# PCB_Sensor_Board_2_x_BME280_680_ATH10_HD.net
KiCad netlist of a schematic drawn in EAGLE
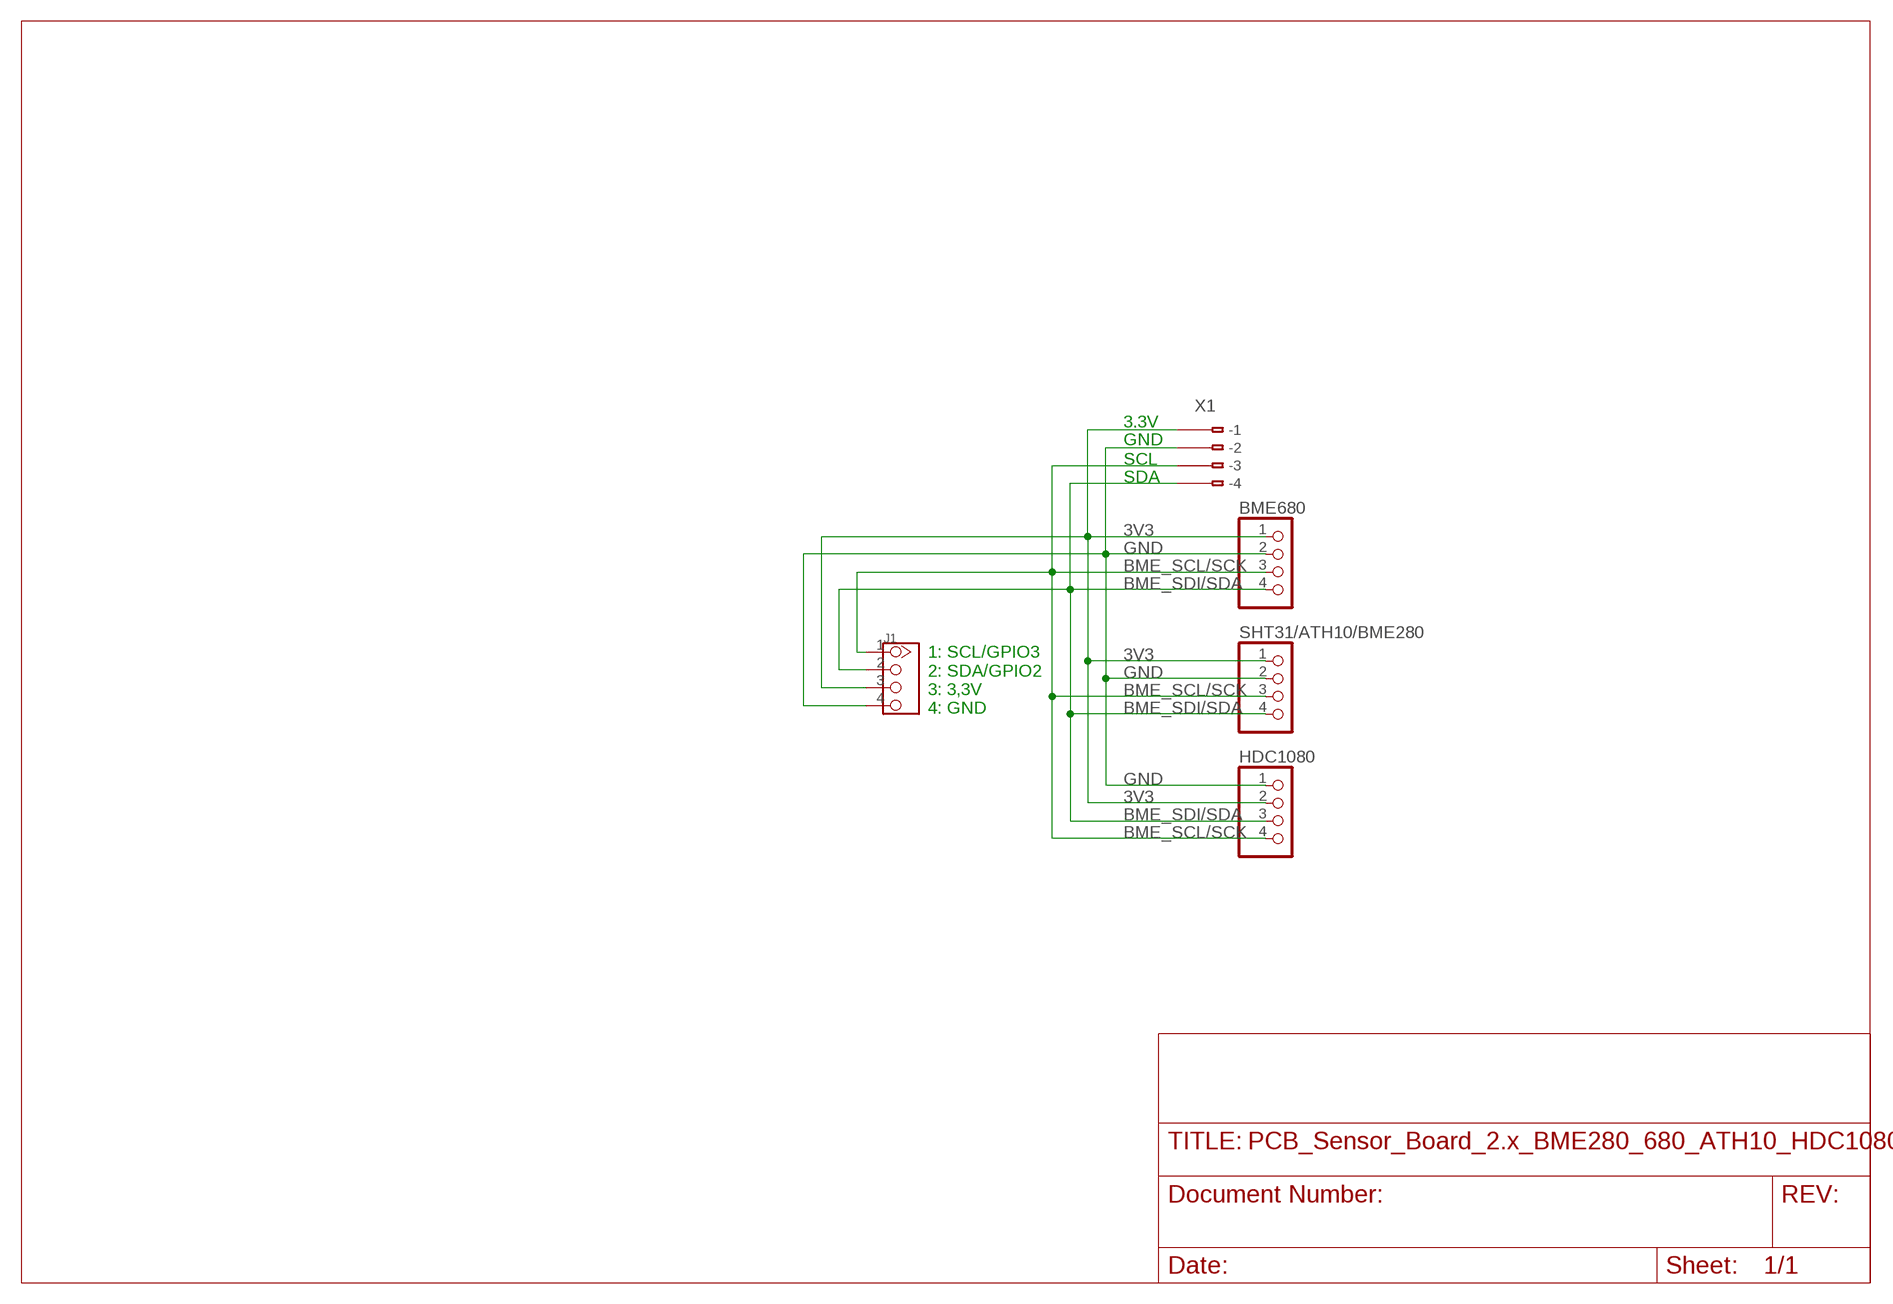
[diagram p0: schematic, sheet 1]

(export (version "E")
  (design (tool "Eeschema 10.0.6"))
  (components
    (comp (ref "BME680")
      (value "PINHD-1X4")
      (footprint "eagle-import:1X04")
      (libsource (lib "eagle-import") (part "PINHD-1X4"))
    )
    (comp (ref "HDC1080")
      (value "PINHD-1X4")
      (footprint "eagle-import:1X04")
      (libsource (lib "eagle-import") (part "PINHD-1X4"))
    )
    (comp (ref "J1")
      (value "TWIG-4P-2.0-2.0")
      (footprint "eagle-import:4P-2.0")
      (libsource (lib "eagle-import") (part "TWIG-4P-2.0-2.0"))
    )
    (comp (ref "SHT31/ATH10/BME280")
      (value "PINHD-1X4")
      (footprint "eagle-import:1X04")
      (libsource (lib "eagle-import") (part "PINHD-1X4"))
    )
    (comp (ref "X1")
      (value "233-504")
      (footprint "eagle-import:233-504")
      (fields (field (name "MF") "Wago Corporation") (field (name "MPN") "0233-0504"))
      (libsource (lib "eagle-import") (part "233-504"))
    )
  )
  (nets
    (net (code "1") (name "/3V3") (class "Default")
      (node (ref "BME680") (pin "1") (pinfunction "1_1") (pintype "passive"))
      (node (ref "HDC1080") (pin "2") (pinfunction "2_2") (pintype "passive"))
      (node (ref "J1") (pin "3") (pinfunction "3_3") (pintype "bidirectional"))
      (node (ref "SHT31/ATH10/BME280") (pin "1") (pinfunction "1_1") (pintype "passive"))
      (node (ref "X1") (pin "B1") (pinfunction "B-1_B1") (pintype "passive"))
    )
    (net (code "2") (name "/BME_SCL{slash}SCK") (class "Default")
      (node (ref "BME680") (pin "3") (pinfunction "3_3") (pintype "passive"))
      (node (ref "HDC1080") (pin "4") (pinfunction "4_4") (pintype "passive"))
      (node (ref "J1") (pin "1") (pinfunction "1_1") (pintype "bidirectional"))
      (node (ref "SHT31/ATH10/BME280") (pin "3") (pinfunction "3_3") (pintype "passive"))
      (node (ref "X1") (pin "B3") (pinfunction "B-3_B3") (pintype "passive"))
    )
    (net (code "3") (name "/BME_SDI{slash}SDA") (class "Default")
      (node (ref "BME680") (pin "4") (pinfunction "4_4") (pintype "passive"))
      (node (ref "HDC1080") (pin "3") (pinfunction "3_3") (pintype "passive"))
      (node (ref "J1") (pin "2") (pinfunction "2_2") (pintype "bidirectional"))
      (node (ref "SHT31/ATH10/BME280") (pin "4") (pinfunction "4_4") (pintype "passive"))
      (node (ref "X1") (pin "B4") (pinfunction "B-4_B4") (pintype "passive"))
    )
    (net (code "4") (name "/GND") (class "Default")
      (node (ref "BME680") (pin "2") (pinfunction "2_2") (pintype "passive"))
      (node (ref "HDC1080") (pin "1") (pinfunction "1_1") (pintype "passive"))
      (node (ref "J1") (pin "4") (pinfunction "4_4") (pintype "bidirectional"))
      (node (ref "SHT31/ATH10/BME280") (pin "2") (pinfunction "2_2") (pintype "passive"))
      (node (ref "X1") (pin "B2") (pinfunction "B-2_B2") (pintype "passive"))
    )
    (net (code "5") (name "unconnected-(X1--1-PadA1)") (class "Default")
      (node (ref "X1") (pin "A1") (pinfunction "-1_A1") (pintype "passive"))
    )
    (net (code "6") (name "unconnected-(X1--2-PadA2)") (class "Default")
      (node (ref "X1") (pin "A2") (pinfunction "-2_A2") (pintype "passive"))
    )
    (net (code "7") (name "unconnected-(X1--3-PadA3)") (class "Default")
      (node (ref "X1") (pin "A3") (pinfunction "-3_A3") (pintype "passive"))
    )
    (net (code "8") (name "unconnected-(X1--4-PadA4)") (class "Default")
      (node (ref "X1") (pin "A4") (pinfunction "-4_A4") (pintype "passive"))
    )
  )
)
